# WeatherShield_Air.net
KiCad netlist of a schematic drawn in EAGLE
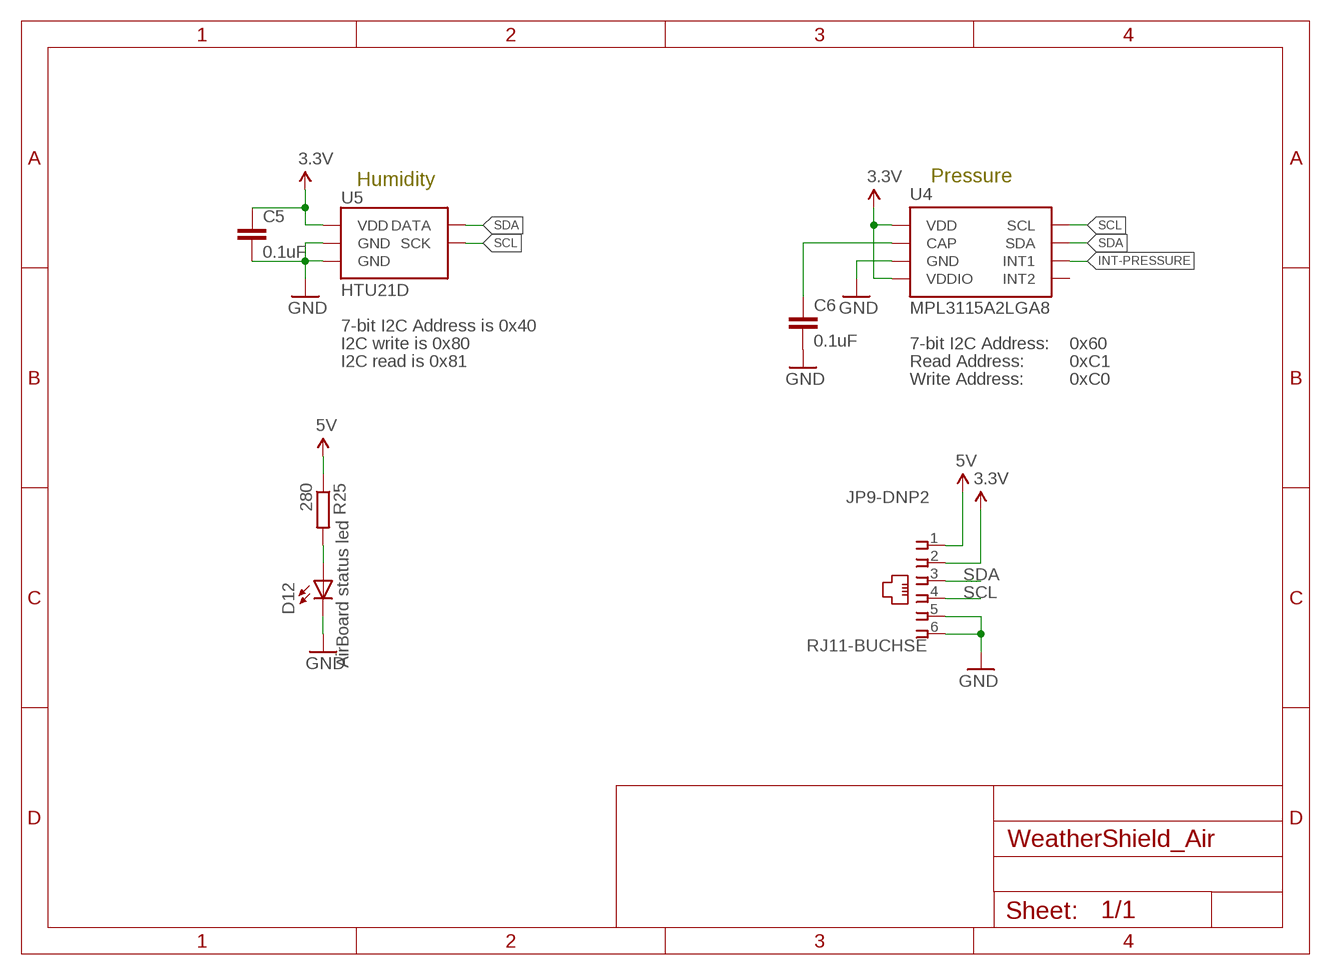
[diagram p0: schematic, sheet 1]

(export (version "E")
  (design (tool "Eeschema 10.0.6"))
  (components
    (comp (ref "C5")
      (value "0.1uF")
      (footprint "eagle-import:C0603")
      (libsource (lib "eagle-import") (part "C-EUC0603"))
    )
    (comp (ref "C6")
      (value "0.1uF")
      (footprint "eagle-import:C0603")
      (libsource (lib "eagle-import") (part "C-EUC0603"))
    )
    (comp (ref "D12")
      (value "AirBoard status led")
      (footprint "eagle-import:LED-0603")
      (libsource (lib "eagle-import") (part "LED0603"))
    )
    (comp (ref "JP9-DNP2")
      (value "RJ11-BUCHSE")
      (footprint "eagle-import:RJ11-STECKER")
      (libsource (lib "eagle-import") (part "RJ11-BUCHSE"))
    )
    (comp (ref "R25")
      (value "280")
      (footprint "eagle-import:R0603")
      (libsource (lib "eagle-import") (part "R-EU_R0603"))
    )
    (comp (ref "U4")
      (value "MPL3115A2LGA8")
      (footprint "eagle-import:LGA8")
      (libsource (lib "eagle-import") (part "MPL3115A2LGA8"))
    )
    (comp (ref "U5")
      (value "HTU21D")
      (footprint "eagle-import:HTU21D")
      (libsource (lib "eagle-import") (part "HTU21DSMD"))
    )
  )
  (nets
    (net (code "1") (name "3.3V") (class "Default")
      (node (ref "C5") (pin "1") (pinfunction "1_1") (pintype "passive"))
      (node (ref "JP9-DNP2") (pin "2") (pinfunction "2_2") (pintype "passive"))
      (node (ref "U4") (pin "1") (pinfunction "VDD_1") (pintype "power_in"))
      (node (ref "U4") (pin "4") (pinfunction "VDDIO_4") (pintype "power_in"))
      (node (ref "U5") (pin "VDD") (pinfunction "VDD_VDD") (pintype "power_in"))
    )
    (net (code "2") (name "5V") (class "Default")
      (node (ref "JP9-DNP2") (pin "1") (pinfunction "1_1") (pintype "passive"))
      (node (ref "R25") (pin "1") (pinfunction "1_1") (pintype "passive"))
    )
    (net (code "3") (name "GND") (class "Default")
      (node (ref "C5") (pin "2") (pinfunction "2_2") (pintype "passive"))
      (node (ref "C6") (pin "2") (pinfunction "2_2") (pintype "passive"))
      (node (ref "D12") (pin "C") (pinfunction "C_C") (pintype "passive"))
      (node (ref "JP9-DNP2") (pin "5") (pinfunction "5_5") (pintype "passive"))
      (node (ref "JP9-DNP2") (pin "6") (pinfunction "6_6") (pintype "passive"))
      (node (ref "U4") (pin "3") (pinfunction "GND_3") (pintype "power_in"))
      (node (ref "U5") (pin "7") (pinfunction "GND_7") (pintype "power_in"))
      (node (ref "U5") (pin "GND") (pinfunction "GND_GND") (pintype "power_in"))
    )
    (net (code "4") (name "INT-PRESSURE") (class "Default")
      (node (ref "U4") (pin "6") (pinfunction "INT1_6") (pintype "output"))
    )
    (net (code "5") (name "Net-(D12-PadA)") (class "Default")
      (node (ref "D12") (pin "A") (pinfunction "A_A") (pintype "passive"))
      (node (ref "R25") (pin "2") (pinfunction "2_2") (pintype "passive"))
    )
    (net (code "6") (name "Net-(U4-CAP)") (class "Default")
      (node (ref "C6") (pin "1") (pinfunction "1_1") (pintype "passive"))
      (node (ref "U4") (pin "2") (pinfunction "CAP_2") (pintype "power_in"))
    )
    (net (code "7") (name "SCL") (class "Default")
      (node (ref "JP9-DNP2") (pin "4") (pinfunction "4_4") (pintype "passive"))
      (node (ref "U4") (pin "8") (pinfunction "SCL_8") (pintype "bidirectional"))
      (node (ref "U5") (pin "SCK") (pinfunction "SCK_SCK") (pintype "input"))
    )
    (net (code "8") (name "SDA") (class "Default")
      (node (ref "JP9-DNP2") (pin "3") (pinfunction "3_3") (pintype "passive"))
      (node (ref "U4") (pin "7") (pinfunction "SDA_7") (pintype "bidirectional"))
      (node (ref "U5") (pin "DATA") (pinfunction "DATA_DATA") (pintype "bidirectional"))
    )
    (net (code "9") (name "unconnected-(U4-INT2-Pad5)") (class "Default")
      (node (ref "U4") (pin "5") (pinfunction "INT2_5") (pintype "output"))
    )
  )
)
